# LED_RED_Direct_BRIGHT.net
KiCad netlist of a schematic drawn in Altium Designer
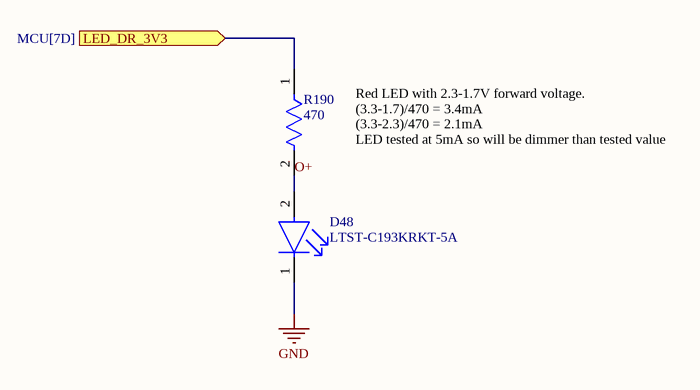
[diagram p0:  LED_RED_Direct_BRIGHT.SchDoc]

(export (version "E")
  (design (tool "Eeschema 10.0.6"))
  (components
    (comp (ref "D48")
      (value "LTST-C193KRKT-5A")
      (footprint "FP-LTST-C193KRKT-5A-MFG")
      (description "Single-color LEDs; LITEON; LTST-C193KRKT-5A; Red; 130 °; 2.3 V; 0603")
      (libsource (lib "HIL RIG FYP") (part "8706943c75ba83719d021d2fdc84c58"))
    )
    (comp (ref "R190")
      (value "470")
      (footprint "FP-CRGCQ0603-IPC_A")
      (description "Res Thick Film 0603 470 Ohm 5% 0.1W(1/10W) ±100ppm/°C Pad SMD T/R Automotive AEC-Q200")
      (fields (field (name "TOLERANCE") "5%") (field (name "Comment") "CRGCQ0603J470R"))
      (libsource (lib "HIL RIG FYP") (part "1029c3af85768c4190bb7ad29bc67b5"))
    )
  )
  (nets
    (net (code "1") (name "/LED_DR_3V3") (class "Default")
      (node (ref "R190") (pin "1") (pinfunction "1_1") (pintype "passive"))
    )
    (net (code "2") (name "/O+") (class "Default")
      (node (ref "D48") (pin "2") (pinfunction "A_2") (pintype "passive"))
      (node (ref "R190") (pin "2") (pinfunction "2_2") (pintype "passive"))
    )
    (net (code "3") (name "GND") (class "Default")
      (node (ref "D48") (pin "1") (pinfunction "C_1") (pintype "passive"))
    )
  )
)
